# BB2LLOAD_SNES.net
KiCad netlist of a schematic drawn in EAGLE
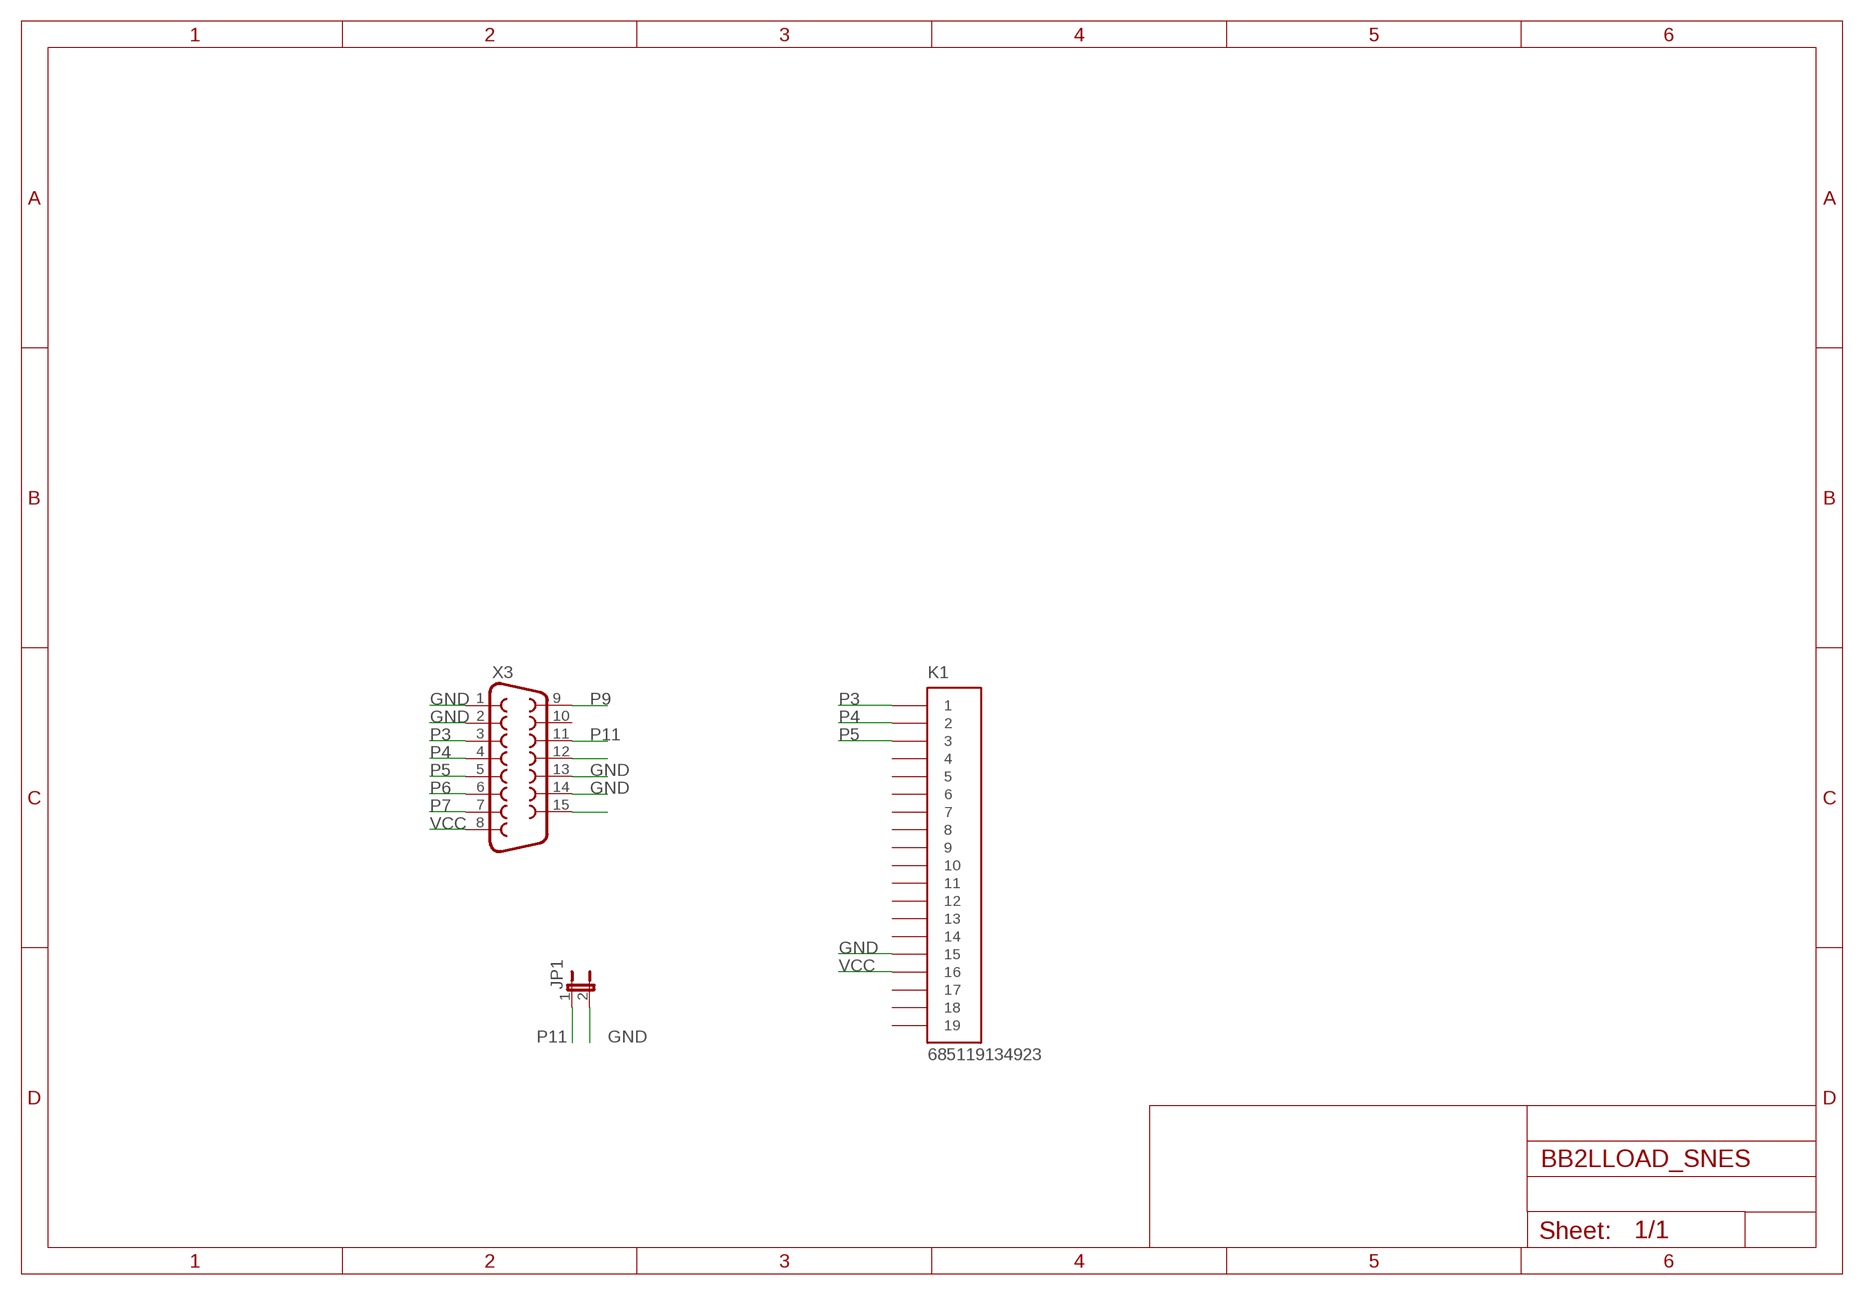
[diagram p0: schematic, sheet 1]

(export (version "E")
  (design (tool "Eeschema 10.0.6"))
  (components
    (comp (ref "JP1")
      (value "JP1E")
      (footprint "eagle-import:JP1")
      (libsource (lib "eagle-import") (part "JP1E"))
    )
    (comp (ref "K1")
      (value "685119134923")
      (footprint "eagle-import:685119134923")
      (libsource (lib "eagle-import") (part "685119134923"))
    )
    (comp (ref "X3")
      (value "F15HP")
      (footprint "eagle-import:F15HP")
      (libsource (lib "eagle-import") (part "F15HP"))
    )
  )
  (nets
    (net (code "1") (name "/GND") (class "Default")
      (node (ref "JP1") (pin "2") (pinfunction "2_2") (pintype "passive"))
      (node (ref "K1") (pin "15") (pinfunction "15_15") (pintype "passive"))
      (node (ref "X3") (pin "1") (pinfunction "1_1") (pintype "passive"))
      (node (ref "X3") (pin "13") (pinfunction "13_13") (pintype "passive"))
      (node (ref "X3") (pin "14") (pinfunction "14_14") (pintype "passive"))
      (node (ref "X3") (pin "2") (pinfunction "2_2") (pintype "passive"))
    )
    (net (code "2") (name "/P3") (class "Default")
      (node (ref "K1") (pin "1") (pinfunction "1_1") (pintype "passive"))
      (node (ref "X3") (pin "3") (pinfunction "3_3") (pintype "passive"))
    )
    (net (code "3") (name "/P4") (class "Default")
      (node (ref "K1") (pin "2") (pinfunction "2_2") (pintype "passive"))
      (node (ref "X3") (pin "4") (pinfunction "4_4") (pintype "passive"))
    )
    (net (code "4") (name "/P5") (class "Default")
      (node (ref "K1") (pin "3") (pinfunction "3_3") (pintype "passive"))
      (node (ref "X3") (pin "5") (pinfunction "5_5") (pintype "passive"))
    )
    (net (code "5") (name "/P6") (class "Default")
      (node (ref "X3") (pin "6") (pinfunction "6_6") (pintype "passive"))
    )
    (net (code "6") (name "/P7") (class "Default")
      (node (ref "X3") (pin "7") (pinfunction "7_7") (pintype "passive"))
    )
    (net (code "7") (name "/P9") (class "Default")
      (node (ref "X3") (pin "9") (pinfunction "9_9") (pintype "passive"))
    )
    (net (code "8") (name "/P11") (class "Default")
      (node (ref "JP1") (pin "1") (pinfunction "1_1") (pintype "passive"))
      (node (ref "X3") (pin "11") (pinfunction "11_11") (pintype "passive"))
    )
    (net (code "9") (name "/VCC") (class "Default")
      (node (ref "K1") (pin "16") (pinfunction "16_16") (pintype "passive"))
      (node (ref "X3") (pin "8") (pinfunction "8_8") (pintype "passive"))
    )
    (net (code "10") (name "unconnected-(K1-Pad4)") (class "Default")
      (node (ref "K1") (pin "4") (pinfunction "4_4") (pintype "passive"))
    )
    (net (code "11") (name "unconnected-(K1-Pad5)") (class "Default")
      (node (ref "K1") (pin "5") (pinfunction "5_5") (pintype "passive"))
    )
    (net (code "12") (name "unconnected-(K1-Pad6)") (class "Default")
      (node (ref "K1") (pin "6") (pinfunction "6_6") (pintype "passive"))
    )
    (net (code "13") (name "unconnected-(K1-Pad7)") (class "Default")
      (node (ref "K1") (pin "7") (pinfunction "7_7") (pintype "passive"))
    )
    (net (code "14") (name "unconnected-(K1-Pad8)") (class "Default")
      (node (ref "K1") (pin "8") (pinfunction "8_8") (pintype "passive"))
    )
    (net (code "15") (name "unconnected-(K1-Pad9)") (class "Default")
      (node (ref "K1") (pin "9") (pinfunction "9_9") (pintype "passive"))
    )
    (net (code "16") (name "unconnected-(K1-Pad10)") (class "Default")
      (node (ref "K1") (pin "10") (pinfunction "10_10") (pintype "passive"))
    )
    (net (code "17") (name "unconnected-(K1-Pad11)") (class "Default")
      (node (ref "K1") (pin "11") (pinfunction "11_11") (pintype "passive"))
    )
    (net (code "18") (name "unconnected-(K1-Pad12)") (class "Default")
      (node (ref "K1") (pin "12") (pinfunction "12_12") (pintype "passive"))
    )
    (net (code "19") (name "unconnected-(K1-Pad13)") (class "Default")
      (node (ref "K1") (pin "13") (pinfunction "13_13") (pintype "passive"))
    )
    (net (code "20") (name "unconnected-(K1-Pad14)") (class "Default")
      (node (ref "K1") (pin "14") (pinfunction "14_14") (pintype "passive"))
    )
    (net (code "21") (name "unconnected-(K1-Pad17)") (class "Default")
      (node (ref "K1") (pin "17") (pinfunction "17_17") (pintype "passive"))
    )
    (net (code "22") (name "unconnected-(K1-Pad18)") (class "Default")
      (node (ref "K1") (pin "18") (pinfunction "18_18") (pintype "passive"))
    )
    (net (code "23") (name "unconnected-(K1-Pad19)") (class "Default")
      (node (ref "K1") (pin "19") (pinfunction "19_19") (pintype "passive"))
    )
    (net (code "24") (name "unconnected-(X3-Pad10)") (class "Default")
      (node (ref "X3") (pin "10") (pinfunction "10_10") (pintype "passive"))
    )
    (net (code "25") (name "unconnected-(X3-Pad12)") (class "Default")
      (node (ref "X3") (pin "12") (pinfunction "12_12") (pintype "passive"))
    )
    (net (code "26") (name "unconnected-(X3-Pad15)") (class "Default")
      (node (ref "X3") (pin "15") (pinfunction "15_15") (pintype "passive"))
    )
  )
)
